# BrainA2-A-11Nov2014.net
KiCad netlist of a schematic drawn in EAGLE
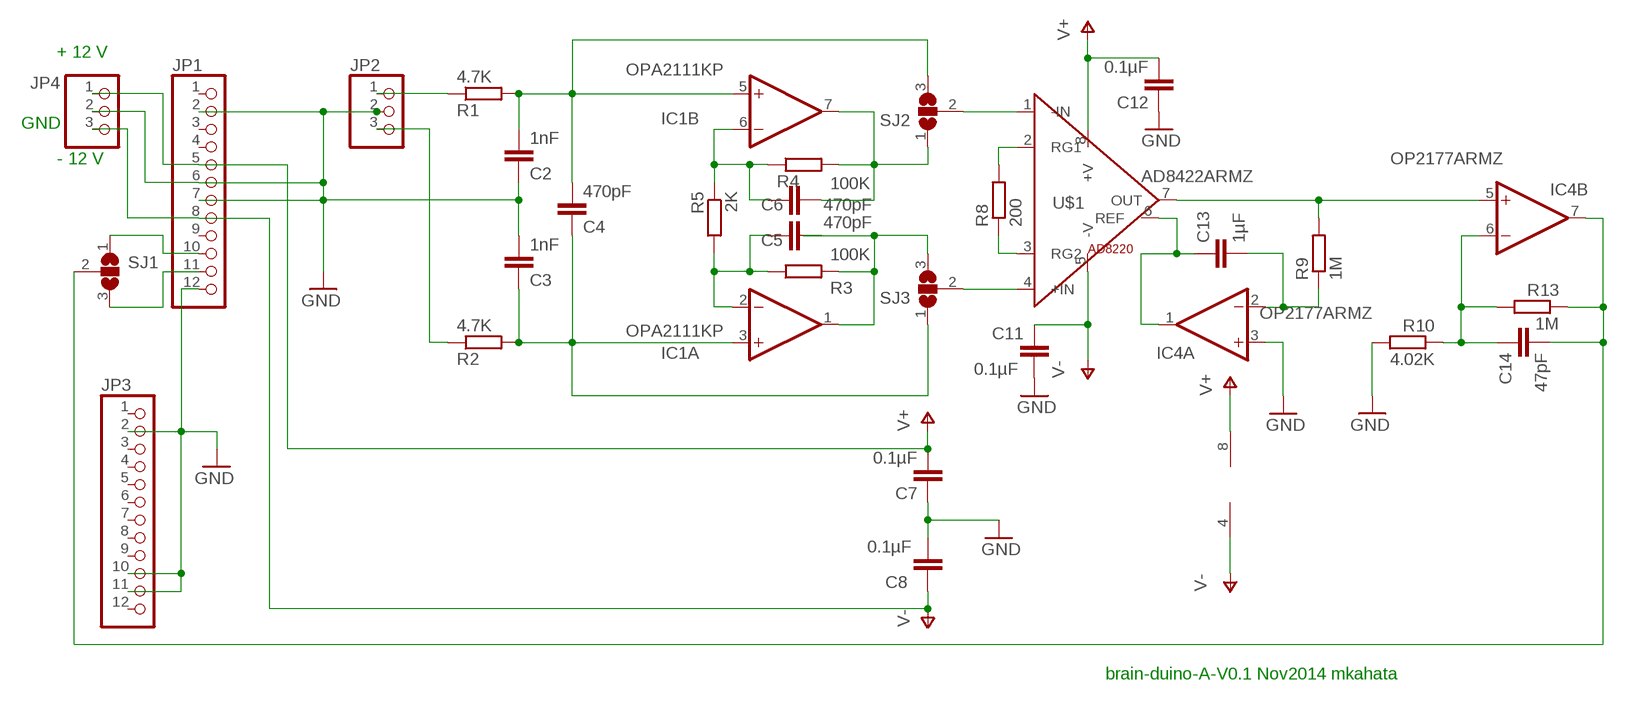
[diagram p0: schematic, sheet 1]

(export (version "E")
  (design (tool "Eeschema 10.0.6"))
  (components
    (comp (ref "C2")
      (value "1nF")
      (footprint "eagle-import:C0603")
      (libsource (lib "eagle-import") (part "C-EUC0603"))
    )
    (comp (ref "C3")
      (value "1nF")
      (footprint "eagle-import:C0603")
      (libsource (lib "eagle-import") (part "C-EUC0603"))
    )
    (comp (ref "C4")
      (value "470pF")
      (footprint "eagle-import:C0603")
      (libsource (lib "eagle-import") (part "C-EUC0603"))
    )
    (comp (ref "C5")
      (value "470pF")
      (footprint "eagle-import:C0603")
      (libsource (lib "eagle-import") (part "C-EUC0603"))
    )
    (comp (ref "C6")
      (value "470pF")
      (footprint "eagle-import:C0603")
      (libsource (lib "eagle-import") (part "C-EUC0603"))
    )
    (comp (ref "C7")
      (value "0.1µF")
      (footprint "eagle-import:C0603")
      (libsource (lib "eagle-import") (part "C-EUC0603"))
    )
    (comp (ref "C8")
      (value "0.1µF")
      (footprint "eagle-import:C0603")
      (libsource (lib "eagle-import") (part "C-EUC0603"))
    )
    (comp (ref "C11")
      (value "0.1µF")
      (footprint "eagle-import:C0603")
      (libsource (lib "eagle-import") (part "C-EUC0603"))
    )
    (comp (ref "C12")
      (value "0.1µF")
      (footprint "eagle-import:C0603")
      (libsource (lib "eagle-import") (part "C-EUC0603"))
    )
    (comp (ref "C13")
      (value "1µF")
      (footprint "eagle-import:C0603")
      (libsource (lib "eagle-import") (part "C-EUC0603"))
    )
    (comp (ref "C14")
      (value "47pF")
      (footprint "eagle-import:C0603")
      (libsource (lib "eagle-import") (part "C-EUC0603"))
    )
    (comp (ref "IC1")
      (value "OPA2111KP")
      (footprint "eagle-import:DIL08")
      (libsource (lib "eagle-import") (part "OPA2111P"))
    )
    (comp (ref "IC4")
      (value "OP2177ARMZ")
      (footprint "eagle-import:MSOP08")
      (libsource (lib "eagle-import") (part "OP1277RM"))
    )
    (comp (ref "JP1")
      (value "PINHD-1X12")
      (footprint "eagle-import:1X12")
      (libsource (lib "eagle-import") (part "PINHD-1X12"))
    )
    (comp (ref "JP2")
      (value "PINHD-1X3")
      (footprint "eagle-import:1X03")
      (libsource (lib "eagle-import") (part "PINHD-1X3"))
    )
    (comp (ref "JP3")
      (value "PINHD-1X12")
      (footprint "eagle-import:1X12")
      (libsource (lib "eagle-import") (part "PINHD-1X12"))
    )
    (comp (ref "JP4")
      (value "PINHD-1X3")
      (footprint "eagle-import:1X03")
      (libsource (lib "eagle-import") (part "PINHD-1X3"))
    )
    (comp (ref "R1")
      (value "4.7K")
      (footprint "eagle-import:R0603")
      (libsource (lib "eagle-import") (part "R-EU_R0603"))
    )
    (comp (ref "R2")
      (value "4.7K")
      (footprint "eagle-import:R0603")
      (libsource (lib "eagle-import") (part "R-EU_R0603"))
    )
    (comp (ref "R3")
      (value "100K")
      (footprint "eagle-import:R0603")
      (libsource (lib "eagle-import") (part "R-EU_R0603"))
    )
    (comp (ref "R4")
      (value "100K")
      (footprint "eagle-import:R0603")
      (libsource (lib "eagle-import") (part "R-EU_R0603"))
    )
    (comp (ref "R5")
      (value "2K")
      (footprint "eagle-import:R0603")
      (libsource (lib "eagle-import") (part "R-EU_R0603"))
    )
    (comp (ref "R8")
      (value "200")
      (footprint "eagle-import:R0603")
      (libsource (lib "eagle-import") (part "R-EU_R0603"))
    )
    (comp (ref "R9")
      (value "1M")
      (footprint "eagle-import:R0603")
      (libsource (lib "eagle-import") (part "R-EU_R0603"))
    )
    (comp (ref "R10")
      (value "4.02K")
      (footprint "eagle-import:R0603")
      (libsource (lib "eagle-import") (part "R-EU_R0603"))
    )
    (comp (ref "R13")
      (value "1M")
      (footprint "eagle-import:R0603")
      (libsource (lib "eagle-import") (part "R-EU_R0603"))
    )
    (comp (ref "SJ1")
      (value "SJ2W")
      (footprint "eagle-import:SJ_2")
      (libsource (lib "eagle-import") (part "SJ2W"))
    )
    (comp (ref "SJ2")
      (value "SJ2W")
      (footprint "eagle-import:SJ_2")
      (libsource (lib "eagle-import") (part "SJ2W"))
    )
    (comp (ref "SJ3")
      (value "SJ2W")
      (footprint "eagle-import:SJ_2")
      (libsource (lib "eagle-import") (part "SJ2W"))
    )
    (comp (ref "U$1")
      (value "AD8422ARMZ")
      (footprint "eagle-import:AD8220")
      (libsource (lib "eagle-import") (part "AD8220"))
    )
  )
  (nets
    (net (code "1") (name "GND") (class "Default")
      (node (ref "C11") (pin "2") (pinfunction "2_2") (pintype "passive"))
      (node (ref "C12") (pin "1") (pinfunction "1_1") (pintype "passive"))
      (node (ref "C2") (pin "1") (pinfunction "1_1") (pintype "passive"))
      (node (ref "C3") (pin "2") (pinfunction "2_2") (pintype "passive"))
      (node (ref "C7") (pin "1") (pinfunction "1_1") (pintype "passive"))
      (node (ref "C8") (pin "2") (pinfunction "2_2") (pintype "passive"))
      (node (ref "IC4") (pin "3") (pinfunction "+IN_3") (pintype "input"))
      (node (ref "JP1") (pin "12") (pinfunction "12_12") (pintype "passive"))
      (node (ref "JP1") (pin "2") (pinfunction "2_2") (pintype "passive"))
      (node (ref "JP1") (pin "6") (pinfunction "6_6") (pintype "passive"))
      (node (ref "JP1") (pin "7") (pinfunction "7_7") (pintype "passive"))
      (node (ref "JP2") (pin "2") (pinfunction "2_2") (pintype "passive"))
      (node (ref "JP3") (pin "10") (pinfunction "10_10") (pintype "passive"))
      (node (ref "JP3") (pin "11") (pinfunction "11_11") (pintype "passive"))
      (node (ref "JP3") (pin "2") (pinfunction "2_2") (pintype "passive"))
      (node (ref "JP4") (pin "2") (pinfunction "2_2") (pintype "passive"))
      (node (ref "R10") (pin "2") (pinfunction "2_2") (pintype "passive"))
    )
    (net (code "2") (name "Net-(IC1A-+IN)") (class "Default")
      (node (ref "C3") (pin "1") (pinfunction "1_1") (pintype "passive"))
      (node (ref "C4") (pin "1") (pinfunction "1_1") (pintype "passive"))
      (node (ref "IC1") (pin "3") (pinfunction "+IN_3") (pintype "input"))
      (node (ref "R2") (pin "2") (pinfunction "2_2") (pintype "passive"))
      (node (ref "SJ3") (pin "1") (pinfunction "1_1") (pintype "passive"))
    )
    (net (code "3") (name "Net-(IC1A--IN)") (class "Default")
      (node (ref "C5") (pin "1") (pinfunction "1_1") (pintype "passive"))
      (node (ref "IC1") (pin "2") (pinfunction "-IN_2") (pintype "input"))
      (node (ref "R3") (pin "1") (pinfunction "1_1") (pintype "passive"))
      (node (ref "R5") (pin "2") (pinfunction "2_2") (pintype "passive"))
    )
    (net (code "4") (name "Net-(IC1A-OUT)") (class "Default")
      (node (ref "C5") (pin "2") (pinfunction "2_2") (pintype "passive"))
      (node (ref "IC1") (pin "1") (pinfunction "OUT_1") (pintype "output"))
      (node (ref "R3") (pin "2") (pinfunction "2_2") (pintype "passive"))
      (node (ref "SJ3") (pin "3") (pinfunction "3_3") (pintype "passive"))
    )
    (net (code "5") (name "Net-(IC1B-+IN)") (class "Default")
      (node (ref "C2") (pin "2") (pinfunction "2_2") (pintype "passive"))
      (node (ref "C4") (pin "2") (pinfunction "2_2") (pintype "passive"))
      (node (ref "IC1") (pin "5") (pinfunction "+IN_5") (pintype "input"))
      (node (ref "R1") (pin "2") (pinfunction "2_2") (pintype "passive"))
      (node (ref "SJ2") (pin "3") (pinfunction "3_3") (pintype "passive"))
    )
    (net (code "6") (name "Net-(IC1B--IN)") (class "Default")
      (node (ref "C6") (pin "1") (pinfunction "1_1") (pintype "passive"))
      (node (ref "IC1") (pin "6") (pinfunction "-IN_6") (pintype "input"))
      (node (ref "R4") (pin "1") (pinfunction "1_1") (pintype "passive"))
      (node (ref "R5") (pin "1") (pinfunction "1_1") (pintype "passive"))
    )
    (net (code "7") (name "Net-(IC1B-OUT)") (class "Default")
      (node (ref "C6") (pin "2") (pinfunction "2_2") (pintype "passive"))
      (node (ref "IC1") (pin "7") (pinfunction "OUT_7") (pintype "output"))
      (node (ref "R4") (pin "2") (pinfunction "2_2") (pintype "passive"))
      (node (ref "SJ2") (pin "1") (pinfunction "1_1") (pintype "passive"))
    )
    (net (code "8") (name "Net-(IC4A--IN)") (class "Default")
      (node (ref "C13") (pin "2") (pinfunction "2_2") (pintype "passive"))
      (node (ref "IC4") (pin "2") (pinfunction "-IN_2") (pintype "input"))
      (node (ref "R9") (pin "1") (pinfunction "1_1") (pintype "passive"))
    )
    (net (code "9") (name "Net-(IC4A-OUT)") (class "Default")
      (node (ref "C13") (pin "1") (pinfunction "1_1") (pintype "passive"))
      (node (ref "IC4") (pin "1") (pinfunction "OUT_1") (pintype "output"))
      (node (ref "U$1") (pin "6") (pinfunction "REF_6") (pintype "input"))
    )
    (net (code "10") (name "Net-(IC4B-+IN)") (class "Default")
      (node (ref "IC4") (pin "5") (pinfunction "+IN_5") (pintype "input"))
      (node (ref "R9") (pin "2") (pinfunction "2_2") (pintype "passive"))
      (node (ref "U$1") (pin "7") (pinfunction "OUT_7") (pintype "input"))
    )
    (net (code "11") (name "Net-(IC4B--IN)") (class "Default")
      (node (ref "C14") (pin "1") (pinfunction "1_1") (pintype "passive"))
      (node (ref "IC4") (pin "6") (pinfunction "-IN_6") (pintype "input"))
      (node (ref "R10") (pin "1") (pinfunction "1_1") (pintype "passive"))
      (node (ref "R13") (pin "2") (pinfunction "2_2") (pintype "passive"))
    )
    (net (code "12") (name "Net-(IC4B-OUT)") (class "Default")
      (node (ref "C14") (pin "2") (pinfunction "2_2") (pintype "passive"))
      (node (ref "IC4") (pin "7") (pinfunction "OUT_7") (pintype "output"))
      (node (ref "R13") (pin "1") (pinfunction "1_1") (pintype "passive"))
      (node (ref "SJ1") (pin "2") (pinfunction "2_2") (pintype "passive"))
    )
    (net (code "13") (name "Net-(JP1-Pad10)") (class "Default")
      (node (ref "JP1") (pin "10") (pinfunction "10_10") (pintype "passive"))
      (node (ref "SJ1") (pin "1") (pinfunction "1_1") (pintype "passive"))
    )
    (net (code "14") (name "Net-(JP1-Pad11)") (class "Default")
      (node (ref "JP1") (pin "11") (pinfunction "11_11") (pintype "passive"))
      (node (ref "SJ1") (pin "3") (pinfunction "3_3") (pintype "passive"))
    )
    (net (code "15") (name "Net-(JP2-Pad1)") (class "Default")
      (node (ref "JP2") (pin "1") (pinfunction "1_1") (pintype "passive"))
      (node (ref "R1") (pin "1") (pinfunction "1_1") (pintype "passive"))
    )
    (net (code "16") (name "Net-(JP2-Pad3)") (class "Default")
      (node (ref "JP2") (pin "3") (pinfunction "3_3") (pintype "passive"))
      (node (ref "R2") (pin "1") (pinfunction "1_1") (pintype "passive"))
    )
    (net (code "17") (name "Net-(U$1-+IN)") (class "Default")
      (node (ref "SJ3") (pin "2") (pinfunction "2_2") (pintype "passive"))
      (node (ref "U$1") (pin "4") (pinfunction "+IN_4") (pintype "passive"))
    )
    (net (code "18") (name "Net-(U$1--IN)") (class "Default")
      (node (ref "SJ2") (pin "2") (pinfunction "2_2") (pintype "passive"))
      (node (ref "U$1") (pin "1") (pinfunction "-IN_1") (pintype "input"))
    )
    (net (code "19") (name "Net-(U$1-RG1)") (class "Default")
      (node (ref "R8") (pin "2") (pinfunction "2_2") (pintype "passive"))
      (node (ref "U$1") (pin "2") (pinfunction "RG1_2") (pintype "input"))
    )
    (net (code "20") (name "Net-(U$1-RG2)") (class "Default")
      (node (ref "R8") (pin "1") (pinfunction "1_1") (pintype "passive"))
      (node (ref "U$1") (pin "3") (pinfunction "RG2_3") (pintype "input"))
    )
    (net (code "21") (name "V+") (class "Default")
      (node (ref "C12") (pin "2") (pinfunction "2_2") (pintype "passive"))
      (node (ref "C7") (pin "2") (pinfunction "2_2") (pintype "passive"))
      (node (ref "IC4") (pin "8") (pinfunction "V+_8") (pintype "power_in"))
      (node (ref "JP1") (pin "5") (pinfunction "5_5") (pintype "passive"))
      (node (ref "JP4") (pin "1") (pinfunction "1_1") (pintype "passive"))
      (node (ref "U$1") (pin "8") (pinfunction "+V_8") (pintype "power_in"))
    )
    (net (code "22") (name "V-") (class "Default")
      (node (ref "C11") (pin "1") (pinfunction "1_1") (pintype "passive"))
      (node (ref "C8") (pin "1") (pinfunction "1_1") (pintype "passive"))
      (node (ref "IC4") (pin "4") (pinfunction "V-_4") (pintype "power_in"))
      (node (ref "JP1") (pin "8") (pinfunction "8_8") (pintype "passive"))
      (node (ref "JP4") (pin "3") (pinfunction "3_3") (pintype "passive"))
      (node (ref "U$1") (pin "5") (pinfunction "-V_5") (pintype "power_in"))
    )
    (net (code "23") (name "unconnected-(JP1-Pad1)") (class "Default")
      (node (ref "JP1") (pin "1") (pinfunction "1_1") (pintype "passive"))
    )
    (net (code "24") (name "unconnected-(JP1-Pad3)") (class "Default")
      (node (ref "JP1") (pin "3") (pinfunction "3_3") (pintype "passive"))
    )
    (net (code "25") (name "unconnected-(JP1-Pad4)") (class "Default")
      (node (ref "JP1") (pin "4") (pinfunction "4_4") (pintype "passive"))
    )
    (net (code "26") (name "unconnected-(JP1-Pad9)") (class "Default")
      (node (ref "JP1") (pin "9") (pinfunction "9_9") (pintype "passive"))
    )
    (net (code "27") (name "unconnected-(JP3-Pad1)") (class "Default")
      (node (ref "JP3") (pin "1") (pinfunction "1_1") (pintype "passive"))
    )
    (net (code "28") (name "unconnected-(JP3-Pad3)") (class "Default")
      (node (ref "JP3") (pin "3") (pinfunction "3_3") (pintype "passive"))
    )
    (net (code "29") (name "unconnected-(JP3-Pad4)") (class "Default")
      (node (ref "JP3") (pin "4") (pinfunction "4_4") (pintype "passive"))
    )
    (net (code "30") (name "unconnected-(JP3-Pad5)") (class "Default")
      (node (ref "JP3") (pin "5") (pinfunction "5_5") (pintype "passive"))
    )
    (net (code "31") (name "unconnected-(JP3-Pad6)") (class "Default")
      (node (ref "JP3") (pin "6") (pinfunction "6_6") (pintype "passive"))
    )
    (net (code "32") (name "unconnected-(JP3-Pad7)") (class "Default")
      (node (ref "JP3") (pin "7") (pinfunction "7_7") (pintype "passive"))
    )
    (net (code "33") (name "unconnected-(JP3-Pad8)") (class "Default")
      (node (ref "JP3") (pin "8") (pinfunction "8_8") (pintype "passive"))
    )
    (net (code "34") (name "unconnected-(JP3-Pad9)") (class "Default")
      (node (ref "JP3") (pin "9") (pinfunction "9_9") (pintype "passive"))
    )
    (net (code "35") (name "unconnected-(JP3-Pad12)") (class "Default")
      (node (ref "JP3") (pin "12") (pinfunction "12_12") (pintype "passive"))
    )
  )
)
